# untitled.net
KiCad netlist of a schematic drawn in EAGLE
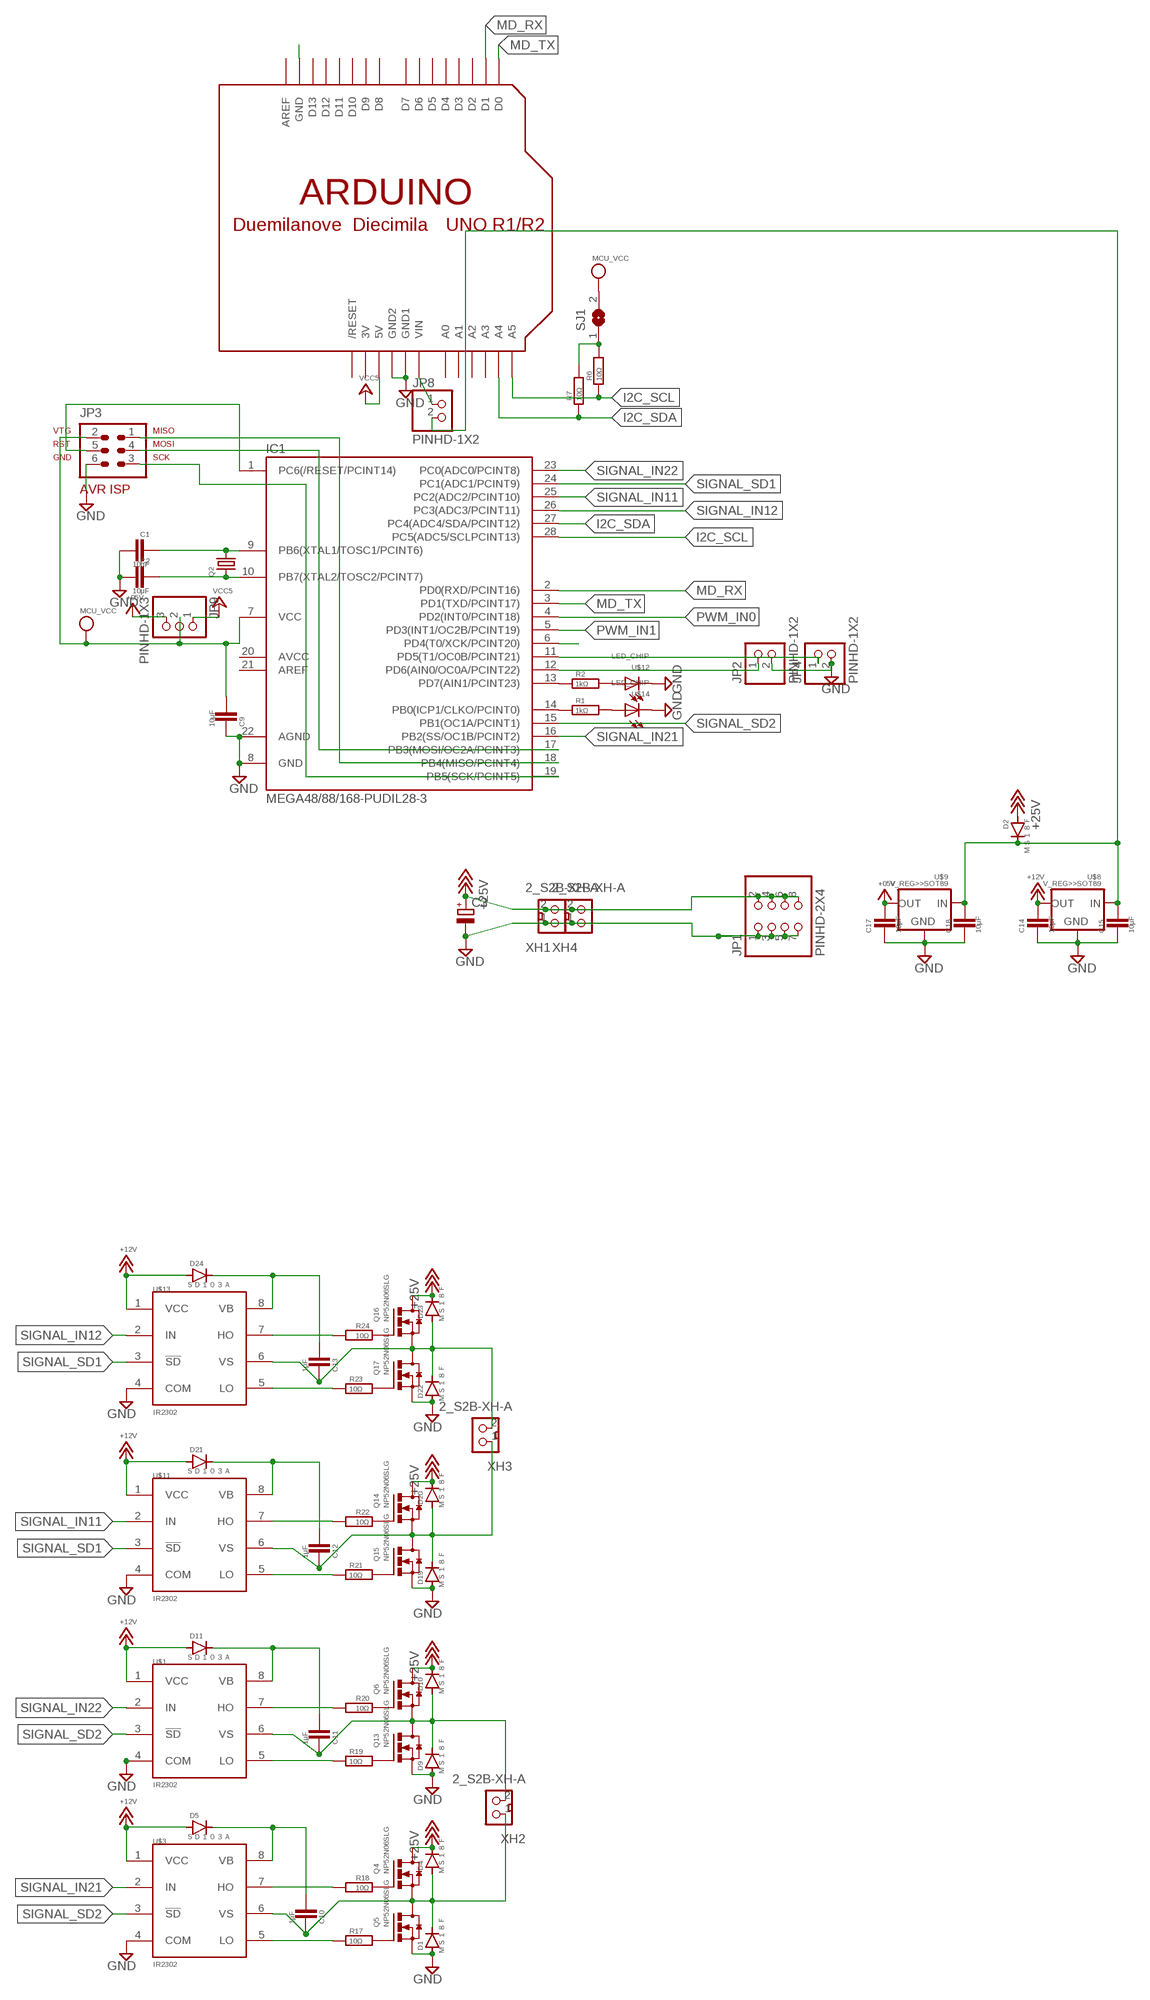
[diagram p0: schematic, sheet 1]

(export (version "E")
  (design (tool "Eeschema 10.0.6"))
  (components
    (comp (ref "C1")
      (value "10μF")
      (footprint "eagle-import:2012")
      (libsource (lib "eagle-import") (part "CAPACITOR{gt}{gt}2012"))
    )
    (comp (ref "C2")
      (value "10μF")
      (footprint "eagle-import:2012")
      (libsource (lib "eagle-import") (part "CAPACITOR{gt}{gt}2012"))
    )
    (comp (ref "C3")
      (value "CPOL-EUUD-6,3X8,8")
      (footprint "eagle-import:UD-6,3X5,8_NICHICON")
      (libsource (lib "eagle-import") (part "CPOL-EUUD-6,3X8,8"))
    )
    (comp (ref "C9")
      (value "10μF")
      (footprint "eagle-import:2012")
      (libsource (lib "eagle-import") (part "CAPACITOR{gt}{gt}2012"))
    )
    (comp (ref "C10")
      (value "1μF")
      (footprint "eagle-import:2012")
      (libsource (lib "eagle-import") (part "CAPACITOR{gt}{gt}2012"))
    )
    (comp (ref "C11")
      (value "1μF")
      (footprint "eagle-import:2012")
      (libsource (lib "eagle-import") (part "CAPACITOR{gt}{gt}2012"))
    )
    (comp (ref "C12")
      (value "1μF")
      (footprint "eagle-import:2012")
      (libsource (lib "eagle-import") (part "CAPACITOR{gt}{gt}2012"))
    )
    (comp (ref "C13")
      (value "1μF")
      (footprint "eagle-import:2012")
      (libsource (lib "eagle-import") (part "CAPACITOR{gt}{gt}2012"))
    )
    (comp (ref "C14")
      (value "10μF")
      (footprint "eagle-import:2012")
      (libsource (lib "eagle-import") (part "CAPACITOR{gt}{gt}2012"))
    )
    (comp (ref "C15")
      (value "10μF")
      (footprint "eagle-import:2012")
      (libsource (lib "eagle-import") (part "CAPACITOR{gt}{gt}2012"))
    )
    (comp (ref "C17")
      (value "10μF")
      (footprint "eagle-import:2012")
      (libsource (lib "eagle-import") (part "CAPACITOR{gt}{gt}2012"))
    )
    (comp (ref "C18")
      (value "10μF")
      (footprint "eagle-import:2012")
      (libsource (lib "eagle-import") (part "CAPACITOR{gt}{gt}2012"))
    )
    (comp (ref "D1")
      (value "ＭＳ１８Ｆ")
      (footprint "eagle-import:MS18F")
      (libsource (lib "eagle-import") (part "DIODE{gt}{gt}MS18F"))
    )
    (comp (ref "D2")
      (value "ＭＳ１８Ｆ")
      (footprint "eagle-import:MS18F")
      (libsource (lib "eagle-import") (part "DIODE{gt}{gt}MS18F"))
    )
    (comp (ref "D4")
      (value "ＭＳ１８Ｆ")
      (footprint "eagle-import:MS18F")
      (libsource (lib "eagle-import") (part "DIODE{gt}{gt}MS18F"))
    )
    (comp (ref "D5")
      (value "ＳＤ１０３Ａ")
      (footprint "eagle-import:SOD123")
      (libsource (lib "eagle-import") (part "DIODE{gt}{gt}SOD123"))
    )
    (comp (ref "D9")
      (value "ＭＳ１８Ｆ")
      (footprint "eagle-import:MS18F")
      (libsource (lib "eagle-import") (part "DIODE{gt}{gt}MS18F"))
    )
    (comp (ref "D10")
      (value "ＭＳ１８Ｆ")
      (footprint "eagle-import:MS18F")
      (libsource (lib "eagle-import") (part "DIODE{gt}{gt}MS18F"))
    )
    (comp (ref "D11")
      (value "ＳＤ１０３Ａ")
      (footprint "eagle-import:SOD123")
      (libsource (lib "eagle-import") (part "DIODE{gt}{gt}SOD123"))
    )
    (comp (ref "D19")
      (value "ＭＳ１８Ｆ")
      (footprint "eagle-import:MS18F")
      (libsource (lib "eagle-import") (part "DIODE{gt}{gt}MS18F"))
    )
    (comp (ref "D20")
      (value "ＭＳ１８Ｆ")
      (footprint "eagle-import:MS18F")
      (libsource (lib "eagle-import") (part "DIODE{gt}{gt}MS18F"))
    )
    (comp (ref "D21")
      (value "ＳＤ１０３Ａ")
      (footprint "eagle-import:SOD123")
      (libsource (lib "eagle-import") (part "DIODE{gt}{gt}SOD123"))
    )
    (comp (ref "D22")
      (value "ＭＳ１８Ｆ")
      (footprint "eagle-import:MS18F")
      (libsource (lib "eagle-import") (part "DIODE{gt}{gt}MS18F"))
    )
    (comp (ref "D23")
      (value "ＭＳ１８Ｆ")
      (footprint "eagle-import:MS18F")
      (libsource (lib "eagle-import") (part "DIODE{gt}{gt}MS18F"))
    )
    (comp (ref "D24")
      (value "ＳＤ１０３Ａ")
      (footprint "eagle-import:SOD123")
      (libsource (lib "eagle-import") (part "DIODE{gt}{gt}SOD123"))
    )
    (comp (ref "IC1")
      (value "MEGA48/88/168-PUDIL28-3")
      (footprint "eagle-import:DIL28-3")
      (libsource (lib "eagle-import") (part "MEGA48/88/168-PUDIL28-3"))
    )
    (comp (ref "JP1")
      (value "PINHD-2X4")
      (footprint "eagle-import:2X04")
      (libsource (lib "eagle-import") (part "PINHD-2X4"))
    )
    (comp (ref "JP2")
      (value "PINHD-1X2")
      (footprint "eagle-import:1X02")
      (libsource (lib "eagle-import") (part "PINHD-1X2"))
    )
    (comp (ref "JP3")
      (value "AVR-ISP-6")
      (footprint "eagle-import:AVR-ISP-6")
      (libsource (lib "eagle-import") (part "AVR-ISP-6"))
    )
    (comp (ref "JP4")
      (value "PINHD-1X2")
      (footprint "eagle-import:1X02")
      (libsource (lib "eagle-import") (part "PINHD-1X2"))
    )
    (comp (ref "JP8")
      (value "PINHD-1X2")
      (footprint "eagle-import:1X02")
      (libsource (lib "eagle-import") (part "PINHD-1X2"))
    )
    (comp (ref "JP9")
      (value "PINHD-1X3")
      (footprint "eagle-import:1X03")
      (libsource (lib "eagle-import") (part "PINHD-1X3"))
    )
    (comp (ref "Q2")
      (value "CRYSTALHC49S")
      (footprint "eagle-import:HC49_S")
      (libsource (lib "eagle-import") (part "CRYSTALHC49S"))
    )
    (comp (ref "Q4")
      (value "NP52N06SLG")
      (footprint "eagle-import:TO252")
      (libsource (lib "eagle-import") (part "MOSFET_N{gt}{gt}TO252"))
    )
    (comp (ref "Q5")
      (value "NP52N06SLG")
      (footprint "eagle-import:TO252")
      (libsource (lib "eagle-import") (part "MOSFET_N{gt}{gt}TO252"))
    )
    (comp (ref "Q6")
      (value "NP52N06SLG")
      (footprint "eagle-import:TO252")
      (libsource (lib "eagle-import") (part "MOSFET_N{gt}{gt}TO252"))
    )
    (comp (ref "Q13")
      (value "NP52N06SLG")
      (footprint "eagle-import:TO252")
      (libsource (lib "eagle-import") (part "MOSFET_N{gt}{gt}TO252"))
    )
    (comp (ref "Q14")
      (value "NP52N06SLG")
      (footprint "eagle-import:TO252")
      (libsource (lib "eagle-import") (part "MOSFET_N{gt}{gt}TO252"))
    )
    (comp (ref "Q15")
      (value "NP52N06SLG")
      (footprint "eagle-import:TO252")
      (libsource (lib "eagle-import") (part "MOSFET_N{gt}{gt}TO252"))
    )
    (comp (ref "Q16")
      (value "NP52N06SLG")
      (footprint "eagle-import:TO252")
      (libsource (lib "eagle-import") (part "MOSFET_N{gt}{gt}TO252"))
    )
    (comp (ref "Q17")
      (value "NP52N06SLG")
      (footprint "eagle-import:TO252")
      (libsource (lib "eagle-import") (part "MOSFET_N{gt}{gt}TO252"))
    )
    (comp (ref "R1")
      (value "1kΩ")
      (footprint "eagle-import:2012")
      (libsource (lib "eagle-import") (part "REGISTER{gt}{gt}2012"))
    )
    (comp (ref "R2")
      (value "1kΩ")
      (footprint "eagle-import:2012")
      (libsource (lib "eagle-import") (part "REGISTER{gt}{gt}2012"))
    )
    (comp (ref "R6")
      (value "10Ω")
      (footprint "eagle-import:2012")
      (libsource (lib "eagle-import") (part "REGISTER{gt}{gt}2012"))
    )
    (comp (ref "R7")
      (value "10Ω")
      (footprint "eagle-import:2012")
      (libsource (lib "eagle-import") (part "REGISTER{gt}{gt}2012"))
    )
    (comp (ref "R17")
      (value "10Ω")
      (footprint "eagle-import:2012")
      (libsource (lib "eagle-import") (part "REGISTER{gt}{gt}2012"))
    )
    (comp (ref "R18")
      (value "10Ω")
      (footprint "eagle-import:2012")
      (libsource (lib "eagle-import") (part "REGISTER{gt}{gt}2012"))
    )
    (comp (ref "R19")
      (value "10Ω")
      (footprint "eagle-import:2012")
      (libsource (lib "eagle-import") (part "REGISTER{gt}{gt}2012"))
    )
    (comp (ref "R20")
      (value "10Ω")
      (footprint "eagle-import:2012")
      (libsource (lib "eagle-import") (part "REGISTER{gt}{gt}2012"))
    )
    (comp (ref "R21")
      (value "10Ω")
      (footprint "eagle-import:2012")
      (libsource (lib "eagle-import") (part "REGISTER{gt}{gt}2012"))
    )
    (comp (ref "R22")
      (value "10Ω")
      (footprint "eagle-import:2012")
      (libsource (lib "eagle-import") (part "REGISTER{gt}{gt}2012"))
    )
    (comp (ref "R23")
      (value "10Ω")
      (footprint "eagle-import:2012")
      (libsource (lib "eagle-import") (part "REGISTER{gt}{gt}2012"))
    )
    (comp (ref "R24")
      (value "10Ω")
      (footprint "eagle-import:2012")
      (libsource (lib "eagle-import") (part "REGISTER{gt}{gt}2012"))
    )
    (comp (ref "SJ1") (value "SJ") (footprint "eagle-import:SJ") (libsource (lib "eagle-import") (part "SJ")))
    (comp (ref "U$1")
      (value "IR2302")
      (footprint "eagle-import:DIL08")
      (libsource (lib "eagle-import") (part "IR2302IR2302"))
    )
    (comp (ref "U$2")
      (value "ARDUINO-NOHOLE")
      (footprint "eagle-import:ARDUINO-NOHOLE")
      (libsource (lib "eagle-import") (part "ARDUINO-NOHOLE"))
    )
    (comp (ref "U$3")
      (value "IR2302")
      (footprint "eagle-import:DIL08")
      (libsource (lib "eagle-import") (part "IR2302IR2302"))
    )
    (comp (ref "U$8")
      (value "V_REG>>SOT89")
      (footprint "eagle-import:SOT89")
      (libsource (lib "eagle-import") (part "V_REG{gt}{gt}SOT89"))
    )
    (comp (ref "U$9")
      (value "V_REG>>SOT89")
      (footprint "eagle-import:SOT89")
      (libsource (lib "eagle-import") (part "V_REG{gt}{gt}SOT89"))
    )
    (comp (ref "U$11")
      (value "IR2302")
      (footprint "eagle-import:DIL08")
      (libsource (lib "eagle-import") (part "IR2302IR2302"))
    )
    (comp (ref "U$12")
      (value "LED_CHIP")
      (footprint "eagle-import:2012")
      (libsource (lib "eagle-import") (part "LED_CHIP"))
    )
    (comp (ref "U$13")
      (value "IR2302")
      (footprint "eagle-import:DIL08")
      (libsource (lib "eagle-import") (part "IR2302IR2302"))
    )
    (comp (ref "U$14")
      (value "LED_CHIP")
      (footprint "eagle-import:2012")
      (libsource (lib "eagle-import") (part "LED_CHIP"))
    )
    (comp (ref "XH1")
      (value "2_S2B-XH-A")
      (footprint "eagle-import:S2B-XH-A")
      (libsource (lib "eagle-import") (part "2_S2B-XH-A"))
    )
    (comp (ref "XH2")
      (value "2_S2B-XH-A")
      (footprint "eagle-import:S2B-XH-A")
      (libsource (lib "eagle-import") (part "2_S2B-XH-A"))
    )
    (comp (ref "XH3")
      (value "2_S2B-XH-A")
      (footprint "eagle-import:S2B-XH-A")
      (libsource (lib "eagle-import") (part "2_S2B-XH-A"))
    )
    (comp (ref "XH4")
      (value "2_S2B-XH-A")
      (footprint "eagle-import:S2B-XH-A")
      (libsource (lib "eagle-import") (part "2_S2B-XH-A"))
    )
  )
  (nets
    (net (code "1") (name "+05V") (class "Default")
      (node (ref "C17") (pin "1") (pinfunction "1_1") (pintype "passive"))
      (node (ref "JP9") (pin "3") (pinfunction "3_3") (pintype "passive"))
      (node (ref "U$9") (pin "1") (pinfunction "OUT_1") (pintype "passive"))
    )
    (net (code "2") (name "+12V") (class "Default")
      (node (ref "C14") (pin "1") (pinfunction "1_1") (pintype "passive"))
      (node (ref "D11") (pin "A") (pinfunction "A_A") (pintype "passive"))
      (node (ref "D21") (pin "A") (pinfunction "A_A") (pintype "passive"))
      (node (ref "D24") (pin "A") (pinfunction "A_A") (pintype "passive"))
      (node (ref "D5") (pin "A") (pinfunction "A_A") (pintype "passive"))
      (node (ref "U$1") (pin "1") (pinfunction "VCC_1") (pintype "bidirectional"))
      (node (ref "U$11") (pin "1") (pinfunction "VCC_1") (pintype "bidirectional"))
      (node (ref "U$13") (pin "1") (pinfunction "VCC_1") (pintype "bidirectional"))
      (node (ref "U$3") (pin "1") (pinfunction "VCC_1") (pintype "bidirectional"))
      (node (ref "U$8") (pin "1") (pinfunction "OUT_1") (pintype "passive"))
    )
    (net (code "3") (name "+25V") (class "Default")
      (node (ref "C3") (pin "+") (pinfunction "+_+") (pintype "passive"))
      (node (ref "D10") (pin "P$2") (pinfunction "C_P$2") (pintype "passive"))
      (node (ref "D2") (pin "P$1") (pinfunction "A_P$1") (pintype "passive"))
      (node (ref "D20") (pin "P$2") (pinfunction "C_P$2") (pintype "passive"))
      (node (ref "D23") (pin "P$2") (pinfunction "C_P$2") (pintype "passive"))
      (node (ref "D4") (pin "P$2") (pinfunction "C_P$2") (pintype "passive"))
      (node (ref "JP1") (pin "2") (pinfunction "2_2") (pintype "passive"))
      (node (ref "JP1") (pin "4") (pinfunction "4_4") (pintype "passive"))
      (node (ref "JP1") (pin "6") (pinfunction "6_6") (pintype "passive"))
      (node (ref "JP1") (pin "8") (pinfunction "8_8") (pintype "passive"))
      (node (ref "Q14") (pin "3") (pinfunction "D_3") (pintype "passive"))
      (node (ref "Q16") (pin "3") (pinfunction "D_3") (pintype "passive"))
      (node (ref "Q4") (pin "3") (pinfunction "D_3") (pintype "passive"))
      (node (ref "Q6") (pin "3") (pinfunction "D_3") (pintype "passive"))
      (node (ref "XH1") (pin "2") (pinfunction "2_2") (pintype "passive"))
      (node (ref "XH4") (pin "2") (pinfunction "2_2") (pintype "passive"))
    )
    (net (code "4") (name "/3V") (class "Default")
      (node (ref "U$2") (pin "3V") (pinfunction "3V_3V") (pintype "power_in"))
    )
    (net (code "5") (name "GND") (class "Default")
      (node (ref "C1") (pin "1") (pinfunction "1_1") (pintype "passive"))
      (node (ref "C14") (pin "2") (pinfunction "2_2") (pintype "passive"))
      (node (ref "C15") (pin "2") (pinfunction "2_2") (pintype "passive"))
      (node (ref "C17") (pin "2") (pinfunction "2_2") (pintype "passive"))
      (node (ref "C18") (pin "2") (pinfunction "2_2") (pintype "passive"))
      (node (ref "C2") (pin "1") (pinfunction "1_1") (pintype "passive"))
      (node (ref "C3") (pin "-") (pinfunction "-_-") (pintype "passive"))
      (node (ref "C9") (pin "2") (pinfunction "2_2") (pintype "passive"))
      (node (ref "D1") (pin "P$1") (pinfunction "A_P$1") (pintype "passive"))
      (node (ref "D19") (pin "P$1") (pinfunction "A_P$1") (pintype "passive"))
      (node (ref "D22") (pin "P$1") (pinfunction "A_P$1") (pintype "passive"))
      (node (ref "D9") (pin "P$1") (pinfunction "A_P$1") (pintype "passive"))
      (node (ref "IC1") (pin "22") (pinfunction "AGND_22") (pintype "power_in"))
      (node (ref "IC1") (pin "8") (pinfunction "GND_8") (pintype "power_in"))
      (node (ref "JP1") (pin "1") (pinfunction "1_1") (pintype "passive"))
      (node (ref "JP1") (pin "3") (pinfunction "3_3") (pintype "passive"))
      (node (ref "JP1") (pin "5") (pinfunction "5_5") (pintype "passive"))
      (node (ref "JP1") (pin "7") (pinfunction "7_7") (pintype "passive"))
      (node (ref "JP2") (pin "2") (pinfunction "2_2") (pintype "passive"))
      (node (ref "JP3") (pin "6") (pinfunction "6_6") (pintype "passive"))
      (node (ref "JP4") (pin "2") (pinfunction "2_2") (pintype "passive"))
      (node (ref "Q13") (pin "2") (pinfunction "S_2") (pintype "passive"))
      (node (ref "Q15") (pin "2") (pinfunction "S_2") (pintype "passive"))
      (node (ref "Q17") (pin "2") (pinfunction "S_2") (pintype "passive"))
      (node (ref "Q5") (pin "2") (pinfunction "S_2") (pintype "passive"))
      (node (ref "U$1") (pin "4") (pinfunction "COM_4") (pintype "bidirectional"))
      (node (ref "U$11") (pin "4") (pinfunction "COM_4") (pintype "bidirectional"))
      (node (ref "U$12") (pin "P$2") (pinfunction "C_P$2") (pintype "passive"))
      (node (ref "U$13") (pin "4") (pinfunction "COM_4") (pintype "bidirectional"))
      (node (ref "U$14") (pin "P$2") (pinfunction "C_P$2") (pintype "passive"))
      (node (ref "U$2") (pin "GND1") (pinfunction "GND1_GND1") (pintype "power_in"))
      (node (ref "U$2") (pin "GND2") (pinfunction "GND2_GND2") (pintype "power_in"))
      (node (ref "U$3") (pin "4") (pinfunction "COM_4") (pintype "bidirectional"))
      (node (ref "U$8") (pin "2") (pinfunction "GND_2") (pintype "input"))
      (node (ref "U$8") (pin "2.1") (pinfunction "GND_2.1") (pintype "input"))
      (node (ref "U$9") (pin "2") (pinfunction "GND_2") (pintype "input"))
      (node (ref "U$9") (pin "2.1") (pinfunction "GND_2.1") (pintype "input"))
      (node (ref "XH1") (pin "1") (pinfunction "1_1") (pintype "passive"))
      (node (ref "XH4") (pin "1") (pinfunction "1_1") (pintype "passive"))
    )
    (net (code "6") (name "I2C_SCL") (class "Default")
      (node (ref "IC1") (pin "28") (pinfunction "PC5(ADC5/SCLPCINT13)_28") (pintype "bidirectional"))
      (node (ref "R6") (pin "1") (pinfunction "1_1") (pintype "passive"))
      (node (ref "U$2") (pin "A5") (pinfunction "A5_A5") (pintype "bidirectional"))
    )
    (net (code "7") (name "I2C_SDA") (class "Default")
      (node (ref "IC1") (pin "27") (pinfunction "PC4(ADC4/SDA/PCINT12)_27") (pintype "bidirectional"))
      (node (ref "R7") (pin "1") (pinfunction "1_1") (pintype "passive"))
      (node (ref "U$2") (pin "A4") (pinfunction "A4_A4") (pintype "bidirectional"))
    )
    (net (code "8") (name "MCU_VCC") (class "Default")
      (node (ref "C9") (pin "1") (pinfunction "1_1") (pintype "passive"))
      (node (ref "IC1") (pin "7") (pinfunction "VCC_7") (pintype "power_in"))
      (node (ref "JP3") (pin "2") (pinfunction "2_2") (pintype "passive"))
      (node (ref "JP9") (pin "2") (pinfunction "2_2") (pintype "passive"))
      (node (ref "SJ1") (pin "2") (pinfunction "2_2") (pintype "passive"))
    )
    (net (code "9") (name "MD_RX") (class "Default")
      (node (ref "IC1") (pin "2") (pinfunction "PD0(RXD/PCINT16)_2") (pintype "bidirectional"))
      (node (ref "U$2") (pin "D1") (pinfunction "D1_D1") (pintype "bidirectional"))
    )
    (net (code "10") (name "MD_TX") (class "Default")
      (node (ref "IC1") (pin "3") (pinfunction "PD1(TXD/PCINT17)_3") (pintype "bidirectional"))
      (node (ref "U$2") (pin "D0") (pinfunction "D0_D0") (pintype "bidirectional"))
    )
    (net (code "11") (name "Net-(D1-C)") (class "Default")
      (node (ref "C10") (pin "2") (pinfunction "2_2") (pintype "passive"))
      (node (ref "D1") (pin "P$2") (pinfunction "C_P$2") (pintype "passive"))
      (node (ref "D4") (pin "P$1") (pinfunction "A_P$1") (pintype "passive"))
      (node (ref "Q4") (pin "2") (pinfunction "S_2") (pintype "passive"))
      (node (ref "Q5") (pin "3") (pinfunction "D_3") (pintype "passive"))
      (node (ref "U$3") (pin "6") (pinfunction "VS_6") (pintype "bidirectional"))
      (node (ref "XH2") (pin "1") (pinfunction "1_1") (pintype "passive"))
    )
    (net (code "12") (name "Net-(D2-C)") (class "Default")
      (node (ref "C15") (pin "1") (pinfunction "1_1") (pintype "passive"))
      (node (ref "C18") (pin "1") (pinfunction "1_1") (pintype "passive"))
      (node (ref "D2") (pin "P$2") (pinfunction "C_P$2") (pintype "passive"))
      (node (ref "JP8") (pin "2") (pinfunction "2_2") (pintype "passive"))
      (node (ref "U$8") (pin "3") (pinfunction "IN_3") (pintype "input"))
      (node (ref "U$9") (pin "3") (pinfunction "IN_3") (pintype "input"))
    )
    (net (code "13") (name "Net-(D10-A)") (class "Default")
      (node (ref "C11") (pin "2") (pinfunction "2_2") (pintype "passive"))
      (node (ref "D10") (pin "P$1") (pinfunction "A_P$1") (pintype "passive"))
      (node (ref "D9") (pin "P$2") (pinfunction "C_P$2") (pintype "passive"))
      (node (ref "Q13") (pin "3") (pinfunction "D_3") (pintype "passive"))
      (node (ref "Q6") (pin "2") (pinfunction "S_2") (pintype "passive"))
      (node (ref "U$1") (pin "6") (pinfunction "VS_6") (pintype "bidirectional"))
      (node (ref "XH2") (pin "2") (pinfunction "2_2") (pintype "passive"))
    )
    (net (code "14") (name "Net-(D19-C)") (class "Default")
      (node (ref "C12") (pin "2") (pinfunction "2_2") (pintype "passive"))
      (node (ref "D19") (pin "P$2") (pinfunction "C_P$2") (pintype "passive"))
      (node (ref "D20") (pin "P$1") (pinfunction "A_P$1") (pintype "passive"))
      (node (ref "Q14") (pin "2") (pinfunction "S_2") (pintype "passive"))
      (node (ref "Q15") (pin "3") (pinfunction "D_3") (pintype "passive"))
      (node (ref "U$11") (pin "6") (pinfunction "VS_6") (pintype "bidirectional"))
      (node (ref "XH3") (pin "1") (pinfunction "1_1") (pintype "passive"))
    )
    (net (code "15") (name "Net-(D22-C)") (class "Default")
      (node (ref "C13") (pin "2") (pinfunction "2_2") (pintype "passive"))
      (node (ref "D22") (pin "P$2") (pinfunction "C_P$2") (pintype "passive"))
      (node (ref "D23") (pin "P$1") (pinfunction "A_P$1") (pintype "passive"))
      (node (ref "Q16") (pin "2") (pinfunction "S_2") (pintype "passive"))
      (node (ref "Q17") (pin "3") (pinfunction "D_3") (pintype "passive"))
      (node (ref "U$13") (pin "6") (pinfunction "VS_6") (pintype "bidirectional"))
      (node (ref "XH3") (pin "2") (pinfunction "2_2") (pintype "passive"))
    )
    (net (code "16") (name "Net-(IC1-PB0(ICP1{slash}CLKO{slash}PCINT0))") (class "Default")
      (node (ref "IC1") (pin "14") (pinfunction "PB0(ICP1/CLKO/PCINT0)_14") (pintype "bidirectional"))
      (node (ref "R1") (pin "1") (pinfunction "1_1") (pintype "passive"))
    )
    (net (code "17") (name "Net-(IC1-PB3(MOSI{slash}OC2A{slash}PCINT3))") (class "Default")
      (node (ref "IC1") (pin "17") (pinfunction "PB3(MOSI/OC2A/PCINT3)_17") (pintype "bidirectional"))
      (node (ref "JP3") (pin "4") (pinfunction "4_4") (pintype "passive"))
    )
    (net (code "18") (name "Net-(IC1-PB4(MISO{slash}PCINT4))") (class "Default")
      (node (ref "IC1") (pin "18") (pinfunction "PB4(MISO/PCINT4)_18") (pintype "bidirectional"))
      (node (ref "JP3") (pin "1") (pinfunction "1_1") (pintype "passive"))
    )
    (net (code "19") (name "Net-(IC1-PB5(SCK{slash}PCINT5))") (class "Default")
      (node (ref "IC1") (pin "19") (pinfunction "PB5(SCK/PCINT5)_19") (pintype "bidirectional"))
      (node (ref "JP3") (pin "3") (pinfunction "3_3") (pintype "passive"))
    )
    (net (code "20") (name "Net-(IC1-PB6(XTAL1{slash}TOSC1{slash}PCINT6))") (class "Default")
      (node (ref "C1") (pin "2") (pinfunction "2_2") (pintype "passive"))
      (node (ref "IC1") (pin "9") (pinfunction "PB6(XTAL1/TOSC1/PCINT6)_9") (pintype "bidirectional"))
      (node (ref "Q2") (pin "2") (pinfunction "2_2") (pintype "passive"))
    )
    (net (code "21") (name "Net-(IC1-PB7(XTAL2{slash}TOSC2{slash}PCINT7))") (class "Default")
      (node (ref "C2") (pin "2") (pinfunction "2_2") (pintype "passive"))
      (node (ref "IC1") (pin "10") (pinfunction "PB7(XTAL2/TOSC2/PCINT7)_10") (pintype "bidirectional"))
      (node (ref "Q2") (pin "1") (pinfunction "1_1") (pintype "passive"))
    )
    (net (code "22") (name "Net-(IC1-PC6({slash}RESET{slash}PCINT14))") (class "Default")
      (node (ref "IC1") (pin "1") (pinfunction "PC6(/RESET/PCINT14)_1") (pintype "bidirectional"))
      (node (ref "JP3") (pin "5") (pinfunction "5_5") (pintype "passive"))
    )
    (net (code "23") (name "Net-(IC1-PD5(T1{slash}OC0B{slash}PCINT21))") (class "Default")
      (node (ref "IC1") (pin "11") (pinfunction "PD5(T1/OC0B/PCINT21)_11") (pintype "bidirectional"))
      (node (ref "JP4") (pin "1") (pinfunction "1_1") (pintype "passive"))
    )
    (net (code "24") (name "Net-(IC1-PD6(AIN0{slash}OC0A{slash}PCINT22))") (class "Default")
      (node (ref "IC1") (pin "12") (pinfunction "PD6(AIN0/OC0A/PCINT22)_12") (pintype "bidirectional"))
      (node (ref "JP2") (pin "1") (pinfunction "1_1") (pintype "passive"))
    )
    (net (code "25") (name "Net-(IC1-PD7(AIN1{slash}PCINT23))") (class "Default")
      (node (ref "IC1") (pin "13") (pinfunction "PD7(AIN1/PCINT23)_13") (pintype "bidirectional"))
      (node (ref "R2") (pin "1") (pinfunction "1_1") (pintype "passive"))
    )
    (net (code "26") (name "Net-(JP8-Pad1)") (class "Default")
      (node (ref "JP8") (pin "1") (pinfunction "1_1") (pintype "passive"))
      (node (ref "U$2") (pin "VIN") (pinfunction "VIN_VIN") (pintype "power_in"))
    )
    (net (code "27") (name "Net-(Q4-G)") (class "Default")
      (node (ref "Q4") (pin "1") (pinfunction "G_1") (pintype "passive"))
      (node (ref "R18") (pin "1") (pinfunction "1_1") (pintype "passive"))
    )
    (net (code "28") (name "Net-(Q5-G)") (class "Default")
      (node (ref "Q5") (pin "1") (pinfunction "G_1") (pintype "passive"))
      (node (ref "R17") (pin "2") (pinfunction "2_2") (pintype "passive"))
    )
    (net (code "29") (name "Net-(Q6-G)") (class "Default")
      (node (ref "Q6") (pin "1") (pinfunction "G_1") (pintype "passive"))
      (node (ref "R20") (pin "1") (pinfunction "1_1") (pintype "passive"))
    )
    (net (code "30") (name "Net-(Q13-G)") (class "Default")
      (node (ref "Q13") (pin "1") (pinfunction "G_1") (pintype "passive"))
      (node (ref "R19") (pin "2") (pinfunction "2_2") (pintype "passive"))
    )
    (net (code "31") (name "Net-(Q14-G)") (class "Default")
      (node (ref "Q14") (pin "1") (pinfunction "G_1") (pintype "passive"))
      (node (ref "R22") (pin "1") (pinfunction "1_1") (pintype "passive"))
    )
    (net (code "32") (name "Net-(Q15-G)") (class "Default")
      (node (ref "Q15") (pin "1") (pinfunction "G_1") (pintype "passive"))
      (node (ref "R21") (pin "2") (pinfunction "2_2") (pintype "passive"))
    )
    (net (code "33") (name "Net-(Q16-G)") (class "Default")
      (node (ref "Q16") (pin "1") (pinfunction "G_1") (pintype "passive"))
      (node (ref "R24") (pin "1") (pinfunction "1_1") (pintype "passive"))
    )
    (net (code "34") (name "Net-(Q17-G)") (class "Default")
      (node (ref "Q17") (pin "1") (pinfunction "G_1") (pintype "passive"))
      (node (ref "R23") (pin "2") (pinfunction "2_2") (pintype "passive"))
    )
    (net (code "35") (name "Net-(R6-Pad2)") (class "Default")
      (node (ref "R6") (pin "2") (pinfunction "2_2") (pintype "passive"))
      (node (ref "R7") (pin "2") (pinfunction "2_2") (pintype "passive"))
      (node (ref "SJ1") (pin "1") (pinfunction "1_1") (pintype "passive"))
    )
    (net (code "36") (name "Net-(U$1-HO)") (class "Default")
      (node (ref "R20") (pin "2") (pinfunction "2_2") (pintype "passive"))
      (node (ref "U$1") (pin "7") (pinfunction "HO_7") (pintype "bidirectional"))
    )
    (net (code "37") (name "Net-(U$1-LO)") (class "Default")
      (node (ref "R19") (pin "1") (pinfunction "1_1") (pintype "passive"))
      (node (ref "U$1") (pin "5") (pinfunction "LO_5") (pintype "bidirectional"))
    )
    (net (code "38") (name "Net-(U$1-VB)") (class "Default")
      (node (ref "C11") (pin "1") (pinfunction "1_1") (pintype "passive"))
      (node (ref "D11") (pin "C") (pinfunction "C_C") (pintype "passive"))
      (node (ref "U$1") (pin "8") (pinfunction "VB_8") (pintype "bidirectional"))
    )
    (net (code "39") (name "Net-(U$3-HO)") (class "Default")
      (node (ref "R18") (pin "2") (pinfunction "2_2") (pintype "passive"))
      (node (ref "U$3") (pin "7") (pinfunction "HO_7") (pintype "bidirectional"))
    )
    (net (code "40") (name "Net-(U$3-LO)") (class "Default")
      (node (ref "R17") (pin "1") (pinfunction "1_1") (pintype "passive"))
      (node (ref "U$3") (pin "5") (pinfunction "LO_5") (pintype "bidirectional"))
    )
    (net (code "41") (name "Net-(U$3-VB)") (class "Default")
      (node (ref "C10") (pin "1") (pinfunction "1_1") (pintype "passive"))
      (node (ref "D5") (pin "C") (pinfunction "C_C") (pintype "passive"))
      (node (ref "U$3") (pin "8") (pinfunction "VB_8") (pintype "bidirectional"))
    )
    (net (code "42") (name "Net-(U$11-HO)") (class "Default")
      (node (ref "R22") (pin "2") (pinfunction "2_2") (pintype "passive"))
      (node (ref "U$11") (pin "7") (pinfunction "HO_7") (pintype "bidirectional"))
    )
    (net (code "43") (name "Net-(U$11-LO)") (class "Default")
      (node (ref "R21") (pin "1") (pinfunction "1_1") (pintype "passive"))
      (node (ref "U$11") (pin "5") (pinfunction "LO_5") (pintype "bidirectional"))
    )
    (net (code "44") (name "Net-(U$11-VB)") (class "Default")
      (node (ref "C12") (pin "1") (pinfunction "1_1") (pintype "passive"))
      (node (ref "D21") (pin "C") (pinfunction "C_C") (pintype "passive"))
      (node (ref "U$11") (pin "8") (pinfunction "VB_8") (pintype "bidirectional"))
    )
    (net (code "45") (name "Net-(U$12-A)") (class "Default")
      (node (ref "R2") (pin "2") (pinfunction "2_2") (pintype "passive"))
      (node (ref "U$12") (pin "P$1") (pinfunction "A_P$1") (pintype "passive"))
    )
    (net (code "46") (name "Net-(U$13-HO)") (class "Default")
      (node (ref "R24") (pin "2") (pinfunction "2_2") (pintype "passive"))
      (node (ref "U$13") (pin "7") (pinfunction "HO_7") (pintype "bidirectional"))
    )
    (net (code "47") (name "Net-(U$13-LO)") (class "Default")
      (node (ref "R23") (pin "1") (pinfunction "1_1") (pintype "passive"))
      (node (ref "U$13") (pin "5") (pinfunction "LO_5") (pintype "bidirectional"))
    )
    (net (code "48") (name "Net-(U$13-VB)") (class "Default")
      (node (ref "C13") (pin "1") (pinfunction "1_1") (pintype "passive"))
      (node (ref "D24") (pin "C") (pinfunction "C_C") (pintype "passive"))
      (node (ref "U$13") (pin "8") (pinfunction "VB_8") (pintype "bidirectional"))
    )
    (net (code "49") (name "Net-(U$14-A)") (class "Default")
      (node (ref "R1") (pin "2") (pinfunction "2_2") (pintype "passive"))
      (node (ref "U$14") (pin "P$1") (pinfunction "A_P$1") (pintype "passive"))
    )
    (net (code "50") (name "PWM_IN0") (class "Default")
      (node (ref "IC1") (pin "4") (pinfunction "PD2(INT0/PCINT18)_4") (pintype "bidirectional"))
    )
    (net (code "51") (name "PWM_IN1") (class "Default")
      (node (ref "IC1") (pin "5") (pinfunction "PD3(INT1/OC2B/PCINT19)_5") (pintype "bidirectional"))
    )
    (net (code "52") (name "SIGNAL_IN11") (class "Default")
      (node (ref "IC1") (pin "25") (pinfunction "PC2(ADC2/PCINT10)_25") (pintype "bidirectional"))
      (node (ref "U$11") (pin "2") (pinfunction "IN_2") (pintype "bidirectional"))
    )
    (net (code "53") (name "SIGNAL_IN12") (class "Default")
      (node (ref "IC1") (pin "26") (pinfunction "PC3(ADC3/PCINT11)_26") (pintype "bidirectional"))
      (node (ref "U$13") (pin "2") (pinfunction "IN_2") (pintype "bidirectional"))
    )
    (net (code "54") (name "SIGNAL_IN21") (class "Default")
      (node (ref "IC1") (pin "16") (pinfunction "PB2(SS/OC1B/PCINT2)_16") (pintype "bidirectional"))
      (node (ref "U$3") (pin "2") (pinfunction "IN_2") (pintype "bidirectional"))
    )
    (net (code "55") (name "SIGNAL_IN22") (class "Default")
      (node (ref "IC1") (pin "23") (pinfunction "PC0(ADC0/PCINT8)_23") (pintype "bidirectional"))
      (node (ref "U$1") (pin "2") (pinfunction "IN_2") (pintype "bidirectional"))
    )
    (net (code "56") (name "SIGNAL_SD1") (class "Default")
      (node (ref "IC1") (pin "24") (pinfunction "PC1(ADC1/PCINT9)_24") (pintype "bidirectional"))
      (node (ref "U$11") (pin "3") (pinfunction "~{SD}_3") (pintype "bidirectional"))
      (node (ref "U$13") (pin "3") (pinfunction "~{SD}_3") (pintype "bidirectional"))
    )
    (net (code "57") (name "SIGNAL_SD2") (class "Default")
      (node (ref "IC1") (pin "15") (pinfunction "PB1(OC1A/PCINT1)_15") (pintype "bidirectional"))
      (node (ref "U$1") (pin "3") (pinfunction "~{SD}_3") (pintype "bidirectional"))
      (node (ref "U$3") (pin "3") (pinfunction "~{SD}_3") (pintype "bidirectional"))
    )
    (net (code "58") (name "VCC5") (class "Default")
      (node (ref "JP9") (pin "1") (pinfunction "1_1") (pintype "passive"))
      (node (ref "U$2") (pin "5V") (pinfunction "5V_5V") (pintype "power_in"))
    )
    (net (code "59") (name "unconnected-(IC1-AREF-Pad21)") (class "Default")
      (node (ref "IC1") (pin "21") (pinfunction "AREF_21") (pintype "passive"))
    )
    (net (code "60") (name "unconnected-(IC1-AVCC-Pad20)") (class "Default")
      (node (ref "IC1") (pin "20") (pinfunction "AVCC_20") (pintype "passive"))
    )
    (net (code "61") (name "unconnected-(IC1-PD4(T0{slash}XCK{slash}PCINT20)-Pad6)") (class "Default")
      (node (ref "IC1") (pin "6") (pinfunction "PD4(T0/XCK/PCINT20)_6") (pintype "bidirectional"))
    )
    (net (code "62") (name "unconnected-(U$2-PadA0)") (class "Default")
      (node (ref "U$2") (pin "A0") (pinfunction "A0_A0") (pintype "bidirectional"))
    )
    (net (code "63") (name "unconnected-(U$2-PadA1)") (class "Default")
      (node (ref "U$2") (pin "A1") (pinfunction "A1_A1") (pintype "bidirectional"))
    )
    (net (code "64") (name "unconnected-(U$2-PadA2)") (class "Default")
      (node (ref "U$2") (pin "A2") (pinfunction "A2_A2") (pintype "bidirectional"))
    )
    (net (code "65") (name "unconnected-(U$2-PadA3)") (class "Default")
      (node (ref "U$2") (pin "A3") (pinfunction "A3_A3") (pintype "bidirectional"))
    )
    (net (code "66") (name "unconnected-(U$2-PadAREF)") (class "Default")
      (node (ref "U$2") (pin "AREF") (pinfunction "AREF_AREF") (pintype "bidirectional"))
    )
    (net (code "67") (name "unconnected-(U$2-PadD2)") (class "Default")
      (node (ref "U$2") (pin "D2") (pinfunction "D2_D2") (pintype "bidirectional"))
    )
    (net (code "68") (name "unconnected-(U$2-PadD3)") (class "Default")
      (node (ref "U$2") (pin "D3") (pinfunction "D3_D3") (pintype "bidirectional"))
    )
    (net (code "69") (name "unconnected-(U$2-PadD4)") (class "Default")
      (node (ref "U$2") (pin "D4") (pinfunction "D4_D4") (pintype "bidirectional"))
    )
    (net (code "70") (name "unconnected-(U$2-PadD5)") (class "Default")
      (node (ref "U$2") (pin "D5") (pinfunction "D5_D5") (pintype "bidirectional"))
    )
    (net (code "71") (name "unconnected-(U$2-PadD6)") (class "Default")
      (node (ref "U$2") (pin "D6") (pinfunction "D6_D6") (pintype "bidirectional"))
    )
    (net (code "72") (name "unconnected-(U$2-PadD7)") (class "Default")
      (node (ref "U$2") (pin "D7") (pinfunction "D7_D7") (pintype "bidirectional"))
    )
    (net (code "73") (name "unconnected-(U$2-PadD8)") (class "Default")
      (node (ref "U$2") (pin "D8") (pinfunction "D8_D8") (pintype "bidirectional"))
    )
    (net (code "74") (name "unconnected-(U$2-PadD9)") (class "Default")
      (node (ref "U$2") (pin "D9") (pinfunction "D9_D9") (pintype "bidirectional"))
    )
    (net (code "75") (name "unconnected-(U$2-PadD10)") (class "Default")
      (node (ref "U$2") (pin "D10") (pinfunction "D10_D10") (pintype "bidirectional"))
    )
    (net (code "76") (name "unconnected-(U$2-PadD11)") (class "Default")
      (node (ref "U$2") (pin "D11") (pinfunction "D11_D11") (pintype "bidirectional"))
    )
    (net (code "77") (name "unconnected-(U$2-PadD12)") (class "Default")
      (node (ref "U$2") (pin "D12") (pinfunction "D12_D12") (pintype "bidirectional"))
    )
    (net (code "78") (name "unconnected-(U$2-PadD13)") (class "Default")
      (node (ref "U$2") (pin "D13") (pinfunction "D13_D13") (pintype "bidirectional"))
    )
    (net (code "79") (name "unconnected-(U$2-PadGND)") (class "Default")
      (node (ref "U$2") (pin "GND") (pinfunction "GND_GND") (pintype "power_in"))
    )
    (net (code "80") (name "unconnected-(U$2-{slash}RESET-PadRESET)") (class "Default")
      (node (ref "U$2") (pin "RESET") (pinfunction "/RESET_RESET") (pintype "bidirectional"))
    )
  )
)
